# Power_In_Protection.net
KiCad netlist of a schematic drawn in Altium Designer
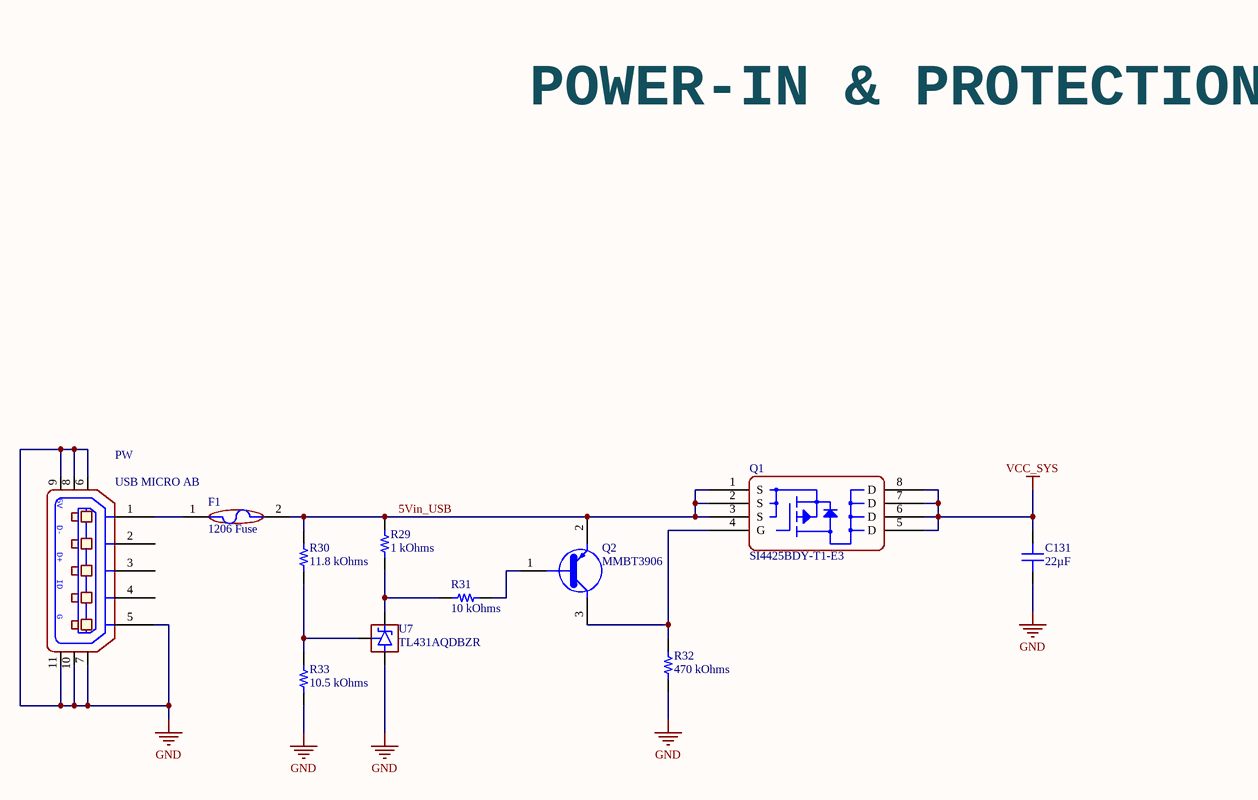
[diagram p0: Power_In_Protection.SchDoc]

(export (version "E")
  (design (tool "Eeschema 10.0.6"))
  (components
    (comp (ref "C131")
      (value "22µF")
      (footprint "CAP 0603_1608")
      (description "CAP CER 22UF 10V X5R 0603")
      (fields (field (name "PART NUMBER") "LMK107BBJ226MA-T") (field (name "MANUFACTURER") "Taiyo Yuden"))
      (libsource (lib "Celestial Altium Library - altium_library") (part "Capacitor"))
    )
    (comp (ref "F1")
      (value "1206 Fuse")
      (footprint "FUSE_1206_3216_0.6MM")
      (description "FUSE BRD MNT 4A 32VAC 63VDC 1206")
      (fields (field (name "MFR_PART_NO") "3413.0222.22") (field (name "MFR") "Schurter Inc."))
      (libsource (lib "AAR_RockChip_RK3328") (part "Mounted_Fuse"))
    )
    (comp (ref "PW")
      (value "USB MICRO AB")
      (footprint "USB_MICRO_AB")
      (description "CONN RCPT MICRO USB AB R/A SMD")
      (fields (field (name "MFR") "Molex Inc") (field (name "MFR_PART_NO") "0475890001"))
      (libsource (lib "AAR_RockChip_RK3328") (part "0475890001"))
    )
    (comp (ref "Q1")
      (value "SI4425BDY-T1-E3")
      (footprint "SO-8")
      (description "MOSFET P-CH 30V 8.8A 8-SOIC")
      (fields
        (field (name "MFR") "Vishay Siliconix")
        (field (name ".CHECKED PCB") "MM")
        (field (name ".CHECKED SCH") "MM")
        (field (name ".CREATOR") "MM")
      )
      (libsource (lib "AAR_RockChip_RK3328") (part "SI4425BDY-T1-E3"))
    )
    (comp (ref "Q2")
      (value "MMBT3906")
      (footprint "SOT23_3_95P240X10-3N")
      (description "Bipolar (BJT) Transistor PNP 40V 200mA 250MHz 250mW Surface Mount TO-236AB")
      (fields
        (field (name "MFR_PART_NO") "MMBT3906,215")
        (field (name "DIGIKEY_PART_NUMBER") "1727-4045-1-ND")
      )
      (libsource (lib "AAR_RockChip_RK3328") (part "MMBT3906"))
    )
    (comp (ref "R29")
      (value "1 kOhms")
      (footprint "RES 1206_3216")
      (description "RES 1K OHM 1% 1/2W 1206")
      (fields
        (field (name "PART NUMBER") "RNCP1206FTD1K00")
        (field (name "MANUFACTURER") "Stackpole Electronics Inc")
      )
      (libsource (lib "Celestial Altium Library - altium_library") (part "Resistor"))
    )
    (comp (ref "R30")
      (value "11.8 kOhms")
      (footprint "RES 0402_1005")
      (description "RES 11.8K OHM 1% 1/16W 0402")
      (fields (field (name "PART NUMBER") "RC0402FR-0711K8L") (field (name "MANUFACTURER") "Yageo"))
      (libsource (lib "Celestial Altium Library - altium_library") (part "Resistor"))
    )
    (comp (ref "R31")
      (value "10 kOhms")
      (footprint "RES 0402_1005")
      (description "RES 10K OHM 0.1% 1/10W 0402")
      (fields
        (field (name "PART NUMBER") "RP73PF1E10KBTD")
        (field (name "MANUFACTURER") "TE Connectivity Passive Product")
      )
      (libsource (lib "Celestial Altium Library - altium_library") (part "Resistor"))
    )
    (comp (ref "R32")
      (value "470 kOhms")
      (footprint "RES 0402_1005")
      (description "RES 470K OHM 1% 1/8W 0402")
      (fields
        (field (name "PART NUMBER") "CRGP0402F470K")
        (field (name "MANUFACTURER") "TE Connectivity Passive Product")
      )
      (libsource (lib "Celestial Altium Library - altium_library") (part "Resistor"))
    )
    (comp (ref "R33")
      (value "10.5 kOhms")
      (footprint "RES 0402_1005")
      (description "RES 10.5K OHM 1% 1/16W 0402")
      (fields (field (name "PART NUMBER") "RC0402FR-0710K5L") (field (name "MANUFACTURER") "Yageo"))
      (libsource (lib "Celestial Altium Library - altium_library") (part "Resistor"))
    )
    (comp (ref "U7")
      (value "TL431AQDBZR")
      (footprint "SOT23-3")
      (description "Shunt Voltage Reference IC 36V ±1% SOT-23-3")
      (fields (field (name "MFR") "Texas Instruments"))
      (libsource (lib "AAR_RockChip_RK3328") (part "TL431AQDBZR"))
    )
  )
  (nets
    (net (code "1") (name "/5Vin_USB") (class "Default")
      (node (ref "F1") (pin "2") (pinfunction "2_2") (pintype "passive"))
      (node (ref "Q1") (pin "1") (pinfunction "S_1") (pintype "passive"))
      (node (ref "Q1") (pin "2") (pinfunction "S_2") (pintype "passive"))
      (node (ref "Q1") (pin "3") (pinfunction "S_3") (pintype "passive"))
      (node (ref "Q2") (pin "2") (pinfunction "2_2") (pintype "passive"))
      (node (ref "R29") (pin "2") (pinfunction "2_2") (pintype "passive"))
      (node (ref "R30") (pin "2") (pinfunction "2_2") (pintype "passive"))
    )
    (net (code "2") (name "GND") (class "Default")
      (node (ref "C131") (pin "1") (pinfunction "1_1") (pintype "passive"))
      (node (ref "PW") (pin "10") (pinfunction "10_10") (pintype "passive"))
      (node (ref "PW") (pin "11") (pinfunction "11_11") (pintype "passive"))
      (node (ref "PW") (pin "5") (pinfunction "P5_5") (pintype "passive"))
      (node (ref "PW") (pin "6") (pinfunction "6_6") (pintype "passive"))
      (node (ref "PW") (pin "7") (pinfunction "7_7") (pintype "passive"))
      (node (ref "PW") (pin "8") (pinfunction "8_8") (pintype "passive"))
      (node (ref "PW") (pin "9") (pinfunction "9_9") (pintype "passive"))
      (node (ref "R32") (pin "1") (pinfunction "1_1") (pintype "passive"))
      (node (ref "R33") (pin "1") (pinfunction "1_1") (pintype "passive"))
      (node (ref "U7") (pin "3") (pinfunction "ANODE_3") (pintype "passive"))
    )
    (net (code "3") (name "Net-(PW-P1)") (class "Default")
      (node (ref "F1") (pin "1") (pinfunction "1_1") (pintype "passive"))
      (node (ref "PW") (pin "1") (pinfunction "P1_1") (pintype "passive"))
    )
    (net (code "4") (name "Net-(Q1-G)") (class "Default")
      (node (ref "Q1") (pin "4") (pinfunction "G_4") (pintype "passive"))
      (node (ref "Q2") (pin "3") (pinfunction "3_3") (pintype "passive"))
      (node (ref "R32") (pin "2") (pinfunction "2_2") (pintype "passive"))
    )
    (net (code "5") (name "Net-(Q2-Pad1)") (class "Default")
      (node (ref "Q2") (pin "1") (pinfunction "1_1") (pintype "passive"))
      (node (ref "R31") (pin "2") (pinfunction "2_2") (pintype "passive"))
    )
    (net (code "6") (name "Net-(U7-CATHODE)") (class "Default")
      (node (ref "R29") (pin "1") (pinfunction "1_1") (pintype "passive"))
      (node (ref "R31") (pin "1") (pinfunction "1_1") (pintype "passive"))
      (node (ref "U7") (pin "1") (pinfunction "CATHODE_1") (pintype "passive"))
    )
    (net (code "7") (name "Net-(U7-REF)") (class "Default")
      (node (ref "R30") (pin "1") (pinfunction "1_1") (pintype "passive"))
      (node (ref "R33") (pin "2") (pinfunction "2_2") (pintype "passive"))
      (node (ref "U7") (pin "2") (pinfunction "REF_2") (pintype "passive"))
    )
    (net (code "8") (name "VCC_SYS") (class "Default")
      (node (ref "C131") (pin "2") (pinfunction "2_2") (pintype "passive"))
      (node (ref "Q1") (pin "5") (pinfunction "D_5") (pintype "passive"))
      (node (ref "Q1") (pin "6") (pinfunction "D_6") (pintype "passive"))
      (node (ref "Q1") (pin "7") (pinfunction "D_7") (pintype "passive"))
      (node (ref "Q1") (pin "8") (pinfunction "D_8") (pintype "passive"))
    )
    (net (code "9") (name "unconnected-(PW-P2-Pad2)") (class "Default")
      (node (ref "PW") (pin "2") (pinfunction "P2_2") (pintype "passive"))
    )
    (net (code "10") (name "unconnected-(PW-P3-Pad3)") (class "Default")
      (node (ref "PW") (pin "3") (pinfunction "P3_3") (pintype "passive"))
    )
    (net (code "11") (name "unconnected-(PW-P4-Pad4)") (class "Default")
      (node (ref "PW") (pin "4") (pinfunction "P4_4") (pintype "passive"))
    )
  )
)
